# band-dsp-feather.net
KiCad netlist of a schematic drawn in EAGLE
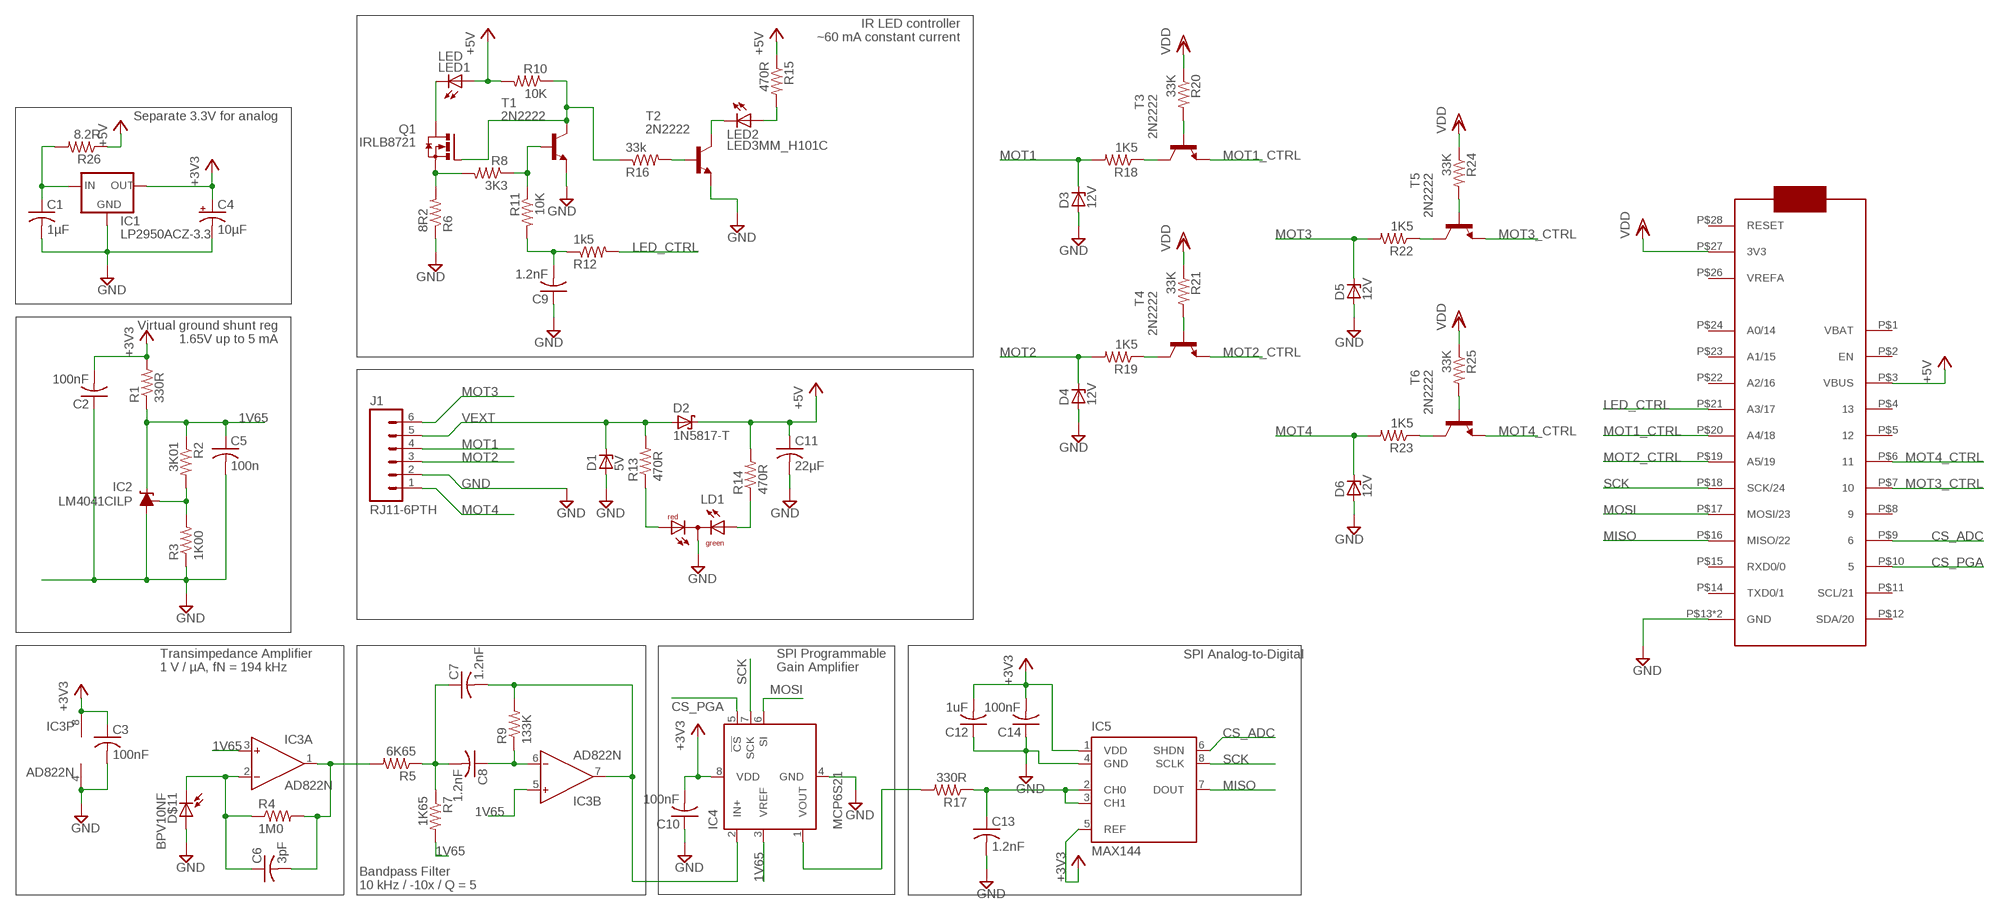
[diagram p0: schematic, sheet 1]

(export (version "E")
  (design (tool "Eeschema 10.0.6"))
  (components
    (comp (ref "C1")
      (value "1µF")
      (footprint "eagle-import:C025-030X050")
      (fields (field (name "MANF") "TDK Corporation"))
      (libsource (lib "eagle-import") (part "C-US025-030X050"))
    )
    (comp (ref "C2")
      (value "100nF")
      (footprint "eagle-import:C025-025X050")
      (fields (field (name "MANF") "Vishay BC Components"))
      (libsource (lib "eagle-import") (part "C-US025-025X050"))
    )
    (comp (ref "C3")
      (value "100nF")
      (footprint "eagle-import:C025-025X050")
      (fields (field (name "MANF") "Vishay BC Components"))
      (libsource (lib "eagle-import") (part "C-US025-025X050"))
    )
    (comp (ref "C4")
      (value "10µF")
      (footprint "eagle-import:E2,5-5")
      (fields (field (name "MANF") "AVX Corporation"))
      (libsource (lib "eagle-import") (part "CPOL-USE2.5-5"))
    )
    (comp (ref "C5")
      (value "100n")
      (footprint "eagle-import:C025-025X050")
      (fields (field (name "MANF") "Vishay BC Components"))
      (libsource (lib "eagle-import") (part "C-US025-025X050"))
    )
    (comp (ref "C6")
      (value "3pF")
      (footprint "eagle-import:C025-024X044")
      (fields (field (name "MANF") "TDK Corporation"))
      (libsource (lib "eagle-import") (part "C-US025-024X044"))
    )
    (comp (ref "C7")
      (value "1.2nF")
      (footprint "eagle-import:C025-025X050")
      (fields (field (name "MANF") "Vishay BC Components"))
      (libsource (lib "eagle-import") (part "C-US025-025X050"))
    )
    (comp (ref "C8")
      (value "1.2nF")
      (footprint "eagle-import:C025-025X050")
      (fields (field (name "MANF") "Vishay BC Components"))
      (libsource (lib "eagle-import") (part "C-US025-025X050"))
    )
    (comp (ref "C9")
      (value "1.2nF")
      (footprint "eagle-import:C025-025X050")
      (fields (field (name "MANF") "Vishay BC Components"))
      (libsource (lib "eagle-import") (part "C-US025-025X050"))
    )
    (comp (ref "C10")
      (value "100nF")
      (footprint "eagle-import:C025-025X050")
      (fields (field (name "MANF") "Vishay BC Components"))
      (libsource (lib "eagle-import") (part "C-US025-025X050"))
    )
    (comp (ref "C11")
      (value "22µF")
      (footprint "eagle-import:C050-045X075")
      (fields (field (name "MANF") "TDK Corporation"))
      (libsource (lib "eagle-import") (part "C-US050-045X075"))
    )
    (comp (ref "C12")
      (value "1uF")
      (footprint "eagle-import:C025-025X050")
      (fields (field (name "MANF") "TDK Corporation"))
      (libsource (lib "eagle-import") (part "C-US025-025X050"))
    )
    (comp (ref "C13")
      (value "1.2nF")
      (footprint "eagle-import:C025-025X050")
      (fields (field (name "MANF") "Vishay BC Components"))
      (libsource (lib "eagle-import") (part "C-US025-025X050"))
    )
    (comp (ref "C14")
      (value "100nF")
      (footprint "eagle-import:C025-025X050")
      (fields (field (name "MANF") "Vishay BC Components"))
      (libsource (lib "eagle-import") (part "C-US025-025X050"))
    )
    (comp (ref "D$11")
      (value "BPV10NF")
      (footprint "eagle-import:LED5MM")
      (fields (field (name "MANF") "Vishay Semiconductor Opto Division"))
      (libsource (lib "eagle-import") (part "BPV10NF"))
    )
    (comp (ref "D1")
      (value "5V")
      (footprint "eagle-import:F126Z10")
      (fields (field (name "MANF") "Littelfuse Inc."))
      (libsource (lib "eagle-import") (part "ZENER-DIODEF126-10"))
    )
    (comp (ref "D2")
      (value "1N5817-T")
      (footprint "eagle-import:DO41-7.6")
      (fields (field (name "MANF") "Fairchild Semiconductor"))
      (libsource (lib "eagle-import") (part "1N5817-T"))
    )
    (comp (ref "D3")
      (value "12V")
      (footprint "eagle-import:F126Z10")
      (fields (field (name "MANF") "Littelfuse Inc."))
      (libsource (lib "eagle-import") (part "ZENER-DIODEF126-10"))
    )
    (comp (ref "D4")
      (value "12V")
      (footprint "eagle-import:F126Z10")
      (fields (field (name "MANF") "Littelfuse Inc."))
      (libsource (lib "eagle-import") (part "ZENER-DIODEF126-10"))
    )
    (comp (ref "D5")
      (value "12V")
      (footprint "eagle-import:F126Z10")
      (fields (field (name "MANF") "Littelfuse Inc."))
      (libsource (lib "eagle-import") (part "ZENER-DIODEF126-10"))
    )
    (comp (ref "D6")
      (value "12V")
      (footprint "eagle-import:F126Z10")
      (fields (field (name "MANF") "Littelfuse Inc."))
      (libsource (lib "eagle-import") (part "ZENER-DIODEF126-10"))
    )
    (comp (ref "IC1")
      (value "LP2950ACZ-3.3")
      (footprint "eagle-import:TO92")
      (fields (field (name "MANF") "Texas Instruments"))
      (libsource (lib "eagle-import") (part "LP2950?ACZ-3.3"))
    )
    (comp (ref "IC2")
      (value "LM4041CILP")
      (footprint "eagle-import:LP_O-PBCY-W3")
      (fields (field (name "MANF") "Texas Instruments"))
      (libsource (lib "eagle-import") (part "LM4041ILPC"))
    )
    (comp (ref "IC3")
      (value "AD822N")
      (footprint "eagle-import:DIL08")
      (fields
        (field (name "DIGIKEY#") "AD823ANZ-ND")
        (field (name "MANF") "Analog Devices Inc.")
        (field (name "MANF#") "AD823ANZ")
      )
      (libsource (lib "eagle-import") (part "AD822N"))
    )
    (comp (ref "IC4")
      (value "MCP6S21")
      (footprint "eagle-import:DIL08")
      (fields (field (name "MANF") "Microchip Technology"))
      (libsource (lib "eagle-import") (part "MCP6S21"))
    )
    (comp (ref "IC5")
      (value "MAX144")
      (footprint "eagle-import:DIL08")
      (fields (field (name "MANF") "Maxim Integrated"))
      (libsource (lib "eagle-import") (part "MAX144"))
    )
    (comp (ref "IC6")
      (value "FEATHER_M0")
      (footprint "eagle-import:FEATHER_M0")
      (fields (field (name "MANF") "Adafruit Industries LLC"))
      (libsource (lib "eagle-import") (part "FEATHER_M0"))
    )
    (comp (ref "J1")
      (value "RJ11-6PTH")
      (footprint "eagle-import:RJ11-6")
      (fields (field (name "MANF") "Assmann WSW Components"))
      (libsource (lib "eagle-import") (part "RJ11-6PTH"))
    )
    (comp (ref "LD1")
      (value "DUOLED-RG-C")
      (footprint "eagle-import:DUOLED-C-5MM")
      (fields (field (name "MANF") "Kingbright"))
      (libsource (lib "eagle-import") (part "DUOLED-RG-C"))
    )
    (comp (ref "LED1")
      (value "LED")
      (footprint "eagle-import:1X02_3.5MM")
      (fields (field (name "MANF") "OSRAM Opto Semiconductors Inc"))
      (libsource (lib "eagle-import") (part "1X02_3.5MM_LED"))
    )
    (comp (ref "LED2")
      (value "LED3MM_H101C")
      (footprint "eagle-import:LED3MM_H101C")
      (fields (field (name "MANF") "Kingbright"))
      (libsource (lib "eagle-import") (part "LED3MM_H101C"))
    )
    (comp (ref "Q1")
      (value "IRLB8721")
      (footprint "eagle-import:TO220BV")
      (fields (field (name "MANF") "Infineon Technologies"))
      (libsource (lib "eagle-import") (part "IRLB8721"))
    )
    (comp (ref "R1")
      (value "330R")
      (footprint "eagle-import:0207_9")
      (fields (field (name "MANF") "Stackpole Electronics Inc."))
      (libsource (lib "eagle-import") (part "R-US_0207/9"))
    )
    (comp (ref "R2")
      (value "3K01")
      (footprint "eagle-import:0207_9")
      (fields (field (name "MANF") "Stackpole Electronics Inc."))
      (libsource (lib "eagle-import") (part "R-US_0207/9"))
    )
    (comp (ref "R3")
      (value "1K00")
      (footprint "eagle-import:0207_9")
      (fields (field (name "MANF") "Stackpole Electronics Inc."))
      (libsource (lib "eagle-import") (part "R-US_0207/9"))
    )
    (comp (ref "R4")
      (value "1M0")
      (footprint "eagle-import:0207_9")
      (fields (field (name "MANF") "Stackpole Electronics Inc"))
      (libsource (lib "eagle-import") (part "R-US_0207/9"))
    )
    (comp (ref "R5")
      (value "6K65")
      (footprint "eagle-import:0207_9")
      (fields (field (name "MANF") "Yageo"))
      (libsource (lib "eagle-import") (part "R-US_0207/9"))
    )
    (comp (ref "R6")
      (value "8R2")
      (footprint "eagle-import:0207_9")
      (fields (field (name "DIGIKEY#") "S8.2HCT-ND") (field (name "MANF") "Stackpole Electronics Inc."))
      (libsource (lib "eagle-import") (part "R-US_0207/9"))
    )
    (comp (ref "R7")
      (value "1K65")
      (footprint "eagle-import:0207_9")
      (fields (field (name "MANF") "Yageo"))
      (libsource (lib "eagle-import") (part "R-US_0207/9"))
    )
    (comp (ref "R8")
      (value "3K3")
      (footprint "eagle-import:0207_9")
      (fields (field (name "MANF") "Stackpole Electronics Inc"))
      (libsource (lib "eagle-import") (part "R-US_0207/9"))
    )
    (comp (ref "R9")
      (value "133K")
      (footprint "eagle-import:0207_9")
      (fields (field (name "MANF") "Yageo"))
      (libsource (lib "eagle-import") (part "R-US_0207/9"))
    )
    (comp (ref "R10")
      (value "10K")
      (footprint "eagle-import:0207_9")
      (fields (field (name "MANF") "Stackpole Electronics Inc"))
      (libsource (lib "eagle-import") (part "R-US_0207/9"))
    )
    (comp (ref "R11")
      (value "10K")
      (footprint "eagle-import:0207_9")
      (fields (field (name "MANF") "Stackpole Electronics Inc"))
      (libsource (lib "eagle-import") (part "R-US_0207/9"))
    )
    (comp (ref "R12")
      (value "1k5")
      (footprint "eagle-import:0207_9")
      (fields (field (name "MANF") "Stackpole Electronics Inc"))
      (libsource (lib "eagle-import") (part "R-US_0207/9"))
    )
    (comp (ref "R13")
      (value "470R")
      (footprint "eagle-import:0207_9")
      (fields (field (name "MANF") "Stackpole Electronics Inc."))
      (libsource (lib "eagle-import") (part "R-US_0207/9"))
    )
    (comp (ref "R14")
      (value "470R")
      (footprint "eagle-import:0207_9")
      (fields (field (name "MANF") "Stackpole Electronics Inc."))
      (libsource (lib "eagle-import") (part "R-US_0207/9"))
    )
    (comp (ref "R15")
      (value "470R")
      (footprint "eagle-import:0207_5V")
      (fields (field (name "MANF") "Stackpole Electronics Inc."))
      (libsource (lib "eagle-import") (part "R-US_0207/5V"))
    )
    (comp (ref "R16")
      (value "33k")
      (footprint "eagle-import:0207_9")
      (fields (field (name "MANF") "Stackpole Electronics Inc"))
      (libsource (lib "eagle-import") (part "R-US_0207/9"))
    )
    (comp (ref "R17")
      (value "330R")
      (footprint "eagle-import:0207_9")
      (fields (field (name "MANF") "Stackpole Electronics Inc."))
      (libsource (lib "eagle-import") (part "R-US_0207/9"))
    )
    (comp (ref "R18")
      (value "1K5")
      (footprint "eagle-import:0207_9")
      (fields (field (name "MANF") "Stackpole Electronics Inc."))
      (libsource (lib "eagle-import") (part "R-US_0207/9"))
    )
    (comp (ref "R19")
      (value "1K5")
      (footprint "eagle-import:0207_9")
      (fields (field (name "MANF") "Stackpole Electronics Inc."))
      (libsource (lib "eagle-import") (part "R-US_0207/9"))
    )
    (comp (ref "R20")
      (value "33K")
      (footprint "eagle-import:0207_9")
      (fields (field (name "MANF") "Stackpole Electronics Inc."))
      (libsource (lib "eagle-import") (part "R-US_0207/9"))
    )
    (comp (ref "R21")
      (value "33K")
      (footprint "eagle-import:0207_9")
      (fields (field (name "MANF") "Stackpole Electronics Inc."))
      (libsource (lib "eagle-import") (part "R-US_0207/9"))
    )
    (comp (ref "R22")
      (value "1K5")
      (footprint "eagle-import:0207_9")
      (fields (field (name "MANF") "Stackpole Electronics Inc."))
      (libsource (lib "eagle-import") (part "R-US_0207/9"))
    )
    (comp (ref "R23")
      (value "1K5")
      (footprint "eagle-import:0207_9")
      (fields (field (name "MANF") "Stackpole Electronics Inc."))
      (libsource (lib "eagle-import") (part "R-US_0207/9"))
    )
    (comp (ref "R24")
      (value "33K")
      (footprint "eagle-import:0207_9")
      (fields (field (name "MANF") "Stackpole Electronics Inc."))
      (libsource (lib "eagle-import") (part "R-US_0207/9"))
    )
    (comp (ref "R25")
      (value "33K")
      (footprint "eagle-import:0207_9")
      (fields (field (name "MANF") "Stackpole Electronics Inc."))
      (libsource (lib "eagle-import") (part "R-US_0207/9"))
    )
    (comp (ref "R26")
      (value "8.2R")
      (footprint "eagle-import:0207_9")
      (fields (field (name "MANF") "Stackpole Electronics Inc."))
      (libsource (lib "eagle-import") (part "R-US_0207/9"))
    )
    (comp (ref "T1")
      (value "2N2222")
      (footprint "eagle-import:TO92-EBC-OVAL")
      (fields (field (name "MANF") "Fairchild Semiconductor"))
      (libsource (lib "eagle-import") (part "2N2222"))
    )
    (comp (ref "T2")
      (value "2N2222")
      (footprint "eagle-import:TO92-EBC-OVAL")
      (fields (field (name "MANF") "Fairchild Semiconductor"))
      (libsource (lib "eagle-import") (part "2N2222"))
    )
    (comp (ref "T3")
      (value "2N2222")
      (footprint "eagle-import:TO92-EBC-OVAL")
      (fields (field (name "MANF") "Fairchild Semiconductor"))
      (libsource (lib "eagle-import") (part "2N2222"))
    )
    (comp (ref "T4")
      (value "2N2222")
      (footprint "eagle-import:TO92-EBC-OVAL")
      (fields (field (name "MANF") "Fairchild Semiconductor"))
      (libsource (lib "eagle-import") (part "2N2222"))
    )
    (comp (ref "T5")
      (value "2N2222")
      (footprint "eagle-import:TO92-EBC-OVAL")
      (fields (field (name "MANF") "Fairchild Semiconductor"))
      (libsource (lib "eagle-import") (part "2N2222"))
    )
    (comp (ref "T6")
      (value "2N2222")
      (footprint "eagle-import:TO92-EBC-OVAL")
      (fields (field (name "MANF") "Fairchild Semiconductor"))
      (libsource (lib "eagle-import") (part "2N2222"))
    )
  )
  (nets
    (net (code "1") (name "+3V3") (class "Default")
      (node (ref "C10") (pin "2") (pinfunction "2_2") (pintype "passive"))
      (node (ref "C12") (pin "2") (pinfunction "2_2") (pintype "passive"))
      (node (ref "C14") (pin "2") (pinfunction "2_2") (pintype "passive"))
      (node (ref "C2") (pin "2") (pinfunction "2_2") (pintype "passive"))
      (node (ref "C3") (pin "1") (pinfunction "1_1") (pintype "passive"))
      (node (ref "C4") (pin "+") (pinfunction "+_+") (pintype "passive"))
      (node (ref "IC1") (pin "1") (pinfunction "OUT_1") (pintype "passive"))
      (node (ref "IC3") (pin "8") (pinfunction "V+_8") (pintype "power_in"))
      (node (ref "IC4") (pin "8") (pinfunction "VDD_8") (pintype "power_in"))
      (node (ref "IC5") (pin "1") (pinfunction "VDD_1") (pintype "power_in"))
      (node (ref "IC5") (pin "5") (pinfunction "REF_5") (pintype "input"))
      (node (ref "R1") (pin "2") (pinfunction "2_2") (pintype "passive"))
    )
    (net (code "2") (name "+5V") (class "Default")
      (node (ref "C11") (pin "1") (pinfunction "1_1") (pintype "passive"))
      (node (ref "D2") (pin "C") (pinfunction "C_C") (pintype "passive"))
      (node (ref "IC6") (pin "P$3") (pinfunction "VBUS_P$3") (pintype "bidirectional"))
      (node (ref "LED1") (pin "1A") (pinfunction "A_1A") (pintype "passive"))
      (node (ref "R10") (pin "2") (pinfunction "2_2") (pintype "passive"))
      (node (ref "R14") (pin "2") (pinfunction "2_2") (pintype "passive"))
      (node (ref "R15") (pin "1") (pinfunction "1_1") (pintype "passive"))
      (node (ref "R26") (pin "1") (pinfunction "1_1") (pintype "passive"))
    )
    (net (code "3") (name "/1V65") (class "Default")
      (node (ref "C5") (pin "1") (pinfunction "1_1") (pintype "passive"))
      (node (ref "IC2") (pin "2") (pinfunction "C_2") (pintype "passive"))
      (node (ref "IC3") (pin "3") (pinfunction "IN+_3") (pintype "input"))
      (node (ref "IC3") (pin "5") (pinfunction "IN+_5") (pintype "input"))
      (node (ref "IC4") (pin "3") (pinfunction "VREF_3") (pintype "input"))
      (node (ref "R1") (pin "1") (pinfunction "1_1") (pintype "passive"))
      (node (ref "R2") (pin "1") (pinfunction "1_1") (pintype "passive"))
      (node (ref "R7") (pin "2") (pinfunction "2_2") (pintype "passive"))
    )
    (net (code "4") (name "/CS_ADC") (class "Default")
      (node (ref "IC5") (pin "6") (pinfunction "SHDN_6") (pintype "input"))
      (node (ref "IC6") (pin "P$9") (pinfunction "6_P$9") (pintype "bidirectional"))
    )
    (net (code "5") (name "/CS_PGA") (class "Default")
      (node (ref "IC4") (pin "5") (pinfunction "~{CS}_5") (pintype "input"))
      (node (ref "IC6") (pin "P$10") (pinfunction "5_P$10") (pintype "bidirectional"))
    )
    (net (code "6") (name "/LED_CTRL") (class "Default")
      (node (ref "IC6") (pin "P$21") (pinfunction "A3/17_P$21") (pintype "bidirectional"))
      (node (ref "R12") (pin "2") (pinfunction "2_2") (pintype "passive"))
    )
    (net (code "7") (name "/MISO") (class "Default")
      (node (ref "IC5") (pin "7") (pinfunction "DOUT_7") (pintype "input"))
      (node (ref "IC6") (pin "P$16") (pinfunction "MISO/22_P$16") (pintype "bidirectional"))
    )
    (net (code "8") (name "/MOSI") (class "Default")
      (node (ref "IC4") (pin "6") (pinfunction "SI_6") (pintype "input"))
      (node (ref "IC6") (pin "P$17") (pinfunction "MOSI/23_P$17") (pintype "bidirectional"))
    )
    (net (code "9") (name "/MOT1") (class "Default")
      (node (ref "D3") (pin "C") (pinfunction "C_C") (pintype "passive"))
      (node (ref "J1") (pin "4") (pinfunction "4_4") (pintype "passive"))
      (node (ref "R18") (pin "2") (pinfunction "2_2") (pintype "passive"))
    )
    (net (code "10") (name "/MOT1_CTRL") (class "Default")
      (node (ref "IC6") (pin "P$20") (pinfunction "A4/18_P$20") (pintype "bidirectional"))
      (node (ref "T3") (pin "E") (pinfunction "E_E") (pintype "passive"))
    )
    (net (code "11") (name "/MOT2") (class "Default")
      (node (ref "D4") (pin "C") (pinfunction "C_C") (pintype "passive"))
      (node (ref "J1") (pin "3") (pinfunction "3_3") (pintype "passive"))
      (node (ref "R19") (pin "2") (pinfunction "2_2") (pintype "passive"))
    )
    (net (code "12") (name "/MOT2_CTRL") (class "Default")
      (node (ref "IC6") (pin "P$19") (pinfunction "A5/19_P$19") (pintype "bidirectional"))
      (node (ref "T4") (pin "E") (pinfunction "E_E") (pintype "passive"))
    )
    (net (code "13") (name "/MOT3") (class "Default")
      (node (ref "D5") (pin "C") (pinfunction "C_C") (pintype "passive"))
      (node (ref "J1") (pin "6") (pinfunction "6_6") (pintype "passive"))
      (node (ref "R22") (pin "2") (pinfunction "2_2") (pintype "passive"))
    )
    (net (code "14") (name "/MOT3_CTRL") (class "Default")
      (node (ref "IC6") (pin "P$7") (pinfunction "10_P$7") (pintype "bidirectional"))
      (node (ref "T5") (pin "E") (pinfunction "E_E") (pintype "passive"))
    )
    (net (code "15") (name "/MOT4") (class "Default")
      (node (ref "D6") (pin "C") (pinfunction "C_C") (pintype "passive"))
      (node (ref "J1") (pin "1") (pinfunction "1_1") (pintype "passive"))
      (node (ref "R23") (pin "2") (pinfunction "2_2") (pintype "passive"))
    )
    (net (code "16") (name "/MOT4_CTRL") (class "Default")
      (node (ref "IC6") (pin "P$6") (pinfunction "11_P$6") (pintype "bidirectional"))
      (node (ref "T6") (pin "E") (pinfunction "E_E") (pintype "passive"))
    )
    (net (code "17") (name "/SCK") (class "Default")
      (node (ref "IC4") (pin "7") (pinfunction "SCK_7") (pintype "input"))
      (node (ref "IC5") (pin "8") (pinfunction "SCLK_8") (pintype "input"))
      (node (ref "IC6") (pin "P$18") (pinfunction "SCK/24_P$18") (pintype "bidirectional"))
    )
    (net (code "18") (name "/VEXT") (class "Default")
      (node (ref "D1") (pin "C") (pinfunction "C_C") (pintype "passive"))
      (node (ref "D2") (pin "A") (pinfunction "A_A") (pintype "passive"))
      (node (ref "J1") (pin "5") (pinfunction "5_5") (pintype "passive"))
      (node (ref "R13") (pin "2") (pinfunction "2_2") (pintype "passive"))
    )
    (net (code "19") (name "GND") (class "Default")
      (node (ref "C1") (pin "2") (pinfunction "2_2") (pintype "passive"))
      (node (ref "C10") (pin "1") (pinfunction "1_1") (pintype "passive"))
      (node (ref "C11") (pin "2") (pinfunction "2_2") (pintype "passive"))
      (node (ref "C12") (pin "1") (pinfunction "1_1") (pintype "passive"))
      (node (ref "C13") (pin "2") (pinfunction "2_2") (pintype "passive"))
      (node (ref "C14") (pin "1") (pinfunction "1_1") (pintype "passive"))
      (node (ref "C2") (pin "1") (pinfunction "1_1") (pintype "passive"))
      (node (ref "C3") (pin "2") (pinfunction "2_2") (pintype "passive"))
      (node (ref "C4") (pin "-") (pinfunction "-_-") (pintype "passive"))
      (node (ref "C5") (pin "2") (pinfunction "2_2") (pintype "passive"))
      (node (ref "C9") (pin "1") (pinfunction "1_1") (pintype "passive"))
      (node (ref "D$11") (pin "A") (pinfunction "A_A") (pintype "passive"))
      (node (ref "D1") (pin "A") (pinfunction "A_A") (pintype "passive"))
      (node (ref "D3") (pin "A") (pinfunction "A_A") (pintype "passive"))
      (node (ref "D4") (pin "A") (pinfunction "A_A") (pintype "passive"))
      (node (ref "D5") (pin "A") (pinfunction "A_A") (pintype "passive"))
      (node (ref "D6") (pin "A") (pinfunction "A_A") (pintype "passive"))
      (node (ref "IC1") (pin "2") (pinfunction "GND_2") (pintype "input"))
      (node (ref "IC2") (pin "3") (pinfunction "A_3") (pintype "passive"))
      (node (ref "IC3") (pin "4") (pinfunction "V-_4") (pintype "power_in"))
      (node (ref "IC4") (pin "4") (pinfunction "GND_4") (pintype "power_in"))
      (node (ref "IC5") (pin "4") (pinfunction "GND_4") (pintype "power_in"))
      (node (ref "IC6") (pin "P$13") (pinfunction "GND_P$13") (pintype "bidirectional"))
      (node (ref "IC6") (pin "P$25") (pinfunction "GND_P$25") (pintype "bidirectional"))
      (node (ref "J1") (pin "2") (pinfunction "2_2") (pintype "passive"))
      (node (ref "LD1") (pin "C") (pinfunction "C_C") (pintype "passive"))
      (node (ref "R3") (pin "1") (pinfunction "1_1") (pintype "passive"))
      (node (ref "R6") (pin "1") (pinfunction "1_1") (pintype "passive"))
      (node (ref "T1") (pin "E") (pinfunction "E_E") (pintype "passive"))
      (node (ref "T2") (pin "E") (pinfunction "E_E") (pintype "passive"))
    )
    (net (code "20") (name "Net-(C7-Pad1)") (class "Default")
      (node (ref "C7") (pin "1") (pinfunction "1_1") (pintype "passive"))
      (node (ref "C8") (pin "2") (pinfunction "2_2") (pintype "passive"))
      (node (ref "R5") (pin "1") (pinfunction "1_1") (pintype "passive"))
      (node (ref "R7") (pin "1") (pinfunction "1_1") (pintype "passive"))
    )
    (net (code "21") (name "Net-(C9-Pad2)") (class "Default")
      (node (ref "C9") (pin "2") (pinfunction "2_2") (pintype "passive"))
      (node (ref "R11") (pin "2") (pinfunction "2_2") (pintype "passive"))
      (node (ref "R12") (pin "1") (pinfunction "1_1") (pintype "passive"))
    )
    (net (code "22") (name "Net-(IC1-IN)") (class "Default")
      (node (ref "C1") (pin "1") (pinfunction "1_1") (pintype "passive"))
      (node (ref "IC1") (pin "3") (pinfunction "IN_3") (pintype "input"))
      (node (ref "R26") (pin "2") (pinfunction "2_2") (pintype "passive"))
    )
    (net (code "23") (name "Net-(IC2-FB)") (class "Default")
      (node (ref "IC2") (pin "1") (pinfunction "FB_1") (pintype "passive"))
      (node (ref "R2") (pin "2") (pinfunction "2_2") (pintype "passive"))
      (node (ref "R3") (pin "2") (pinfunction "2_2") (pintype "passive"))
    )
    (net (code "24") (name "Net-(IC3A-IN-)") (class "Default")
      (node (ref "C6") (pin "1") (pinfunction "1_1") (pintype "passive"))
      (node (ref "D$11") (pin "K") (pinfunction "K_K") (pintype "passive"))
      (node (ref "IC3") (pin "2") (pinfunction "IN-_2") (pintype "input"))
      (node (ref "R4") (pin "1") (pinfunction "1_1") (pintype "passive"))
    )
    (net (code "25") (name "Net-(IC3A-OUT)") (class "Default")
      (node (ref "C6") (pin "2") (pinfunction "2_2") (pintype "passive"))
      (node (ref "IC3") (pin "1") (pinfunction "OUT_1") (pintype "output"))
      (node (ref "R4") (pin "2") (pinfunction "2_2") (pintype "passive"))
      (node (ref "R5") (pin "2") (pinfunction "2_2") (pintype "passive"))
    )
    (net (code "26") (name "Net-(IC3B-IN-)") (class "Default")
      (node (ref "C8") (pin "1") (pinfunction "1_1") (pintype "passive"))
      (node (ref "IC3") (pin "6") (pinfunction "IN-_6") (pintype "input"))
      (node (ref "R9") (pin "1") (pinfunction "1_1") (pintype "passive"))
    )
    (net (code "27") (name "Net-(IC3B-OUT)") (class "Default")
      (node (ref "C7") (pin "2") (pinfunction "2_2") (pintype "passive"))
      (node (ref "IC3") (pin "7") (pinfunction "OUT_7") (pintype "output"))
      (node (ref "IC4") (pin "2") (pinfunction "IN+_2") (pintype "input"))
      (node (ref "R9") (pin "2") (pinfunction "2_2") (pintype "passive"))
    )
    (net (code "28") (name "Net-(IC4-VOUT)") (class "Default")
      (node (ref "IC4") (pin "1") (pinfunction "VOUT_1") (pintype "output"))
      (node (ref "R17") (pin "2") (pinfunction "2_2") (pintype "passive"))
    )
    (net (code "29") (name "Net-(IC5-CH0)") (class "Default")
      (node (ref "C13") (pin "1") (pinfunction "1_1") (pintype "passive"))
      (node (ref "IC5") (pin "2") (pinfunction "CH0_2") (pintype "input"))
      (node (ref "IC5") (pin "3") (pinfunction "CH1_3") (pintype "input"))
      (node (ref "R17") (pin "1") (pinfunction "1_1") (pintype "passive"))
    )
    (net (code "30") (name "Net-(LD1-AG)") (class "Default")
      (node (ref "LD1") (pin "AX") (pinfunction "AG_AX") (pintype "passive"))
      (node (ref "R14") (pin "1") (pinfunction "1_1") (pintype "passive"))
    )
    (net (code "31") (name "Net-(LD1-PadAR)") (class "Default")
      (node (ref "LD1") (pin "AR") (pinfunction "AR_AR") (pintype "passive"))
      (node (ref "R13") (pin "1") (pinfunction "1_1") (pintype "passive"))
    )
    (net (code "32") (name "Net-(LED1-K)") (class "Default")
      (node (ref "LED1") (pin "2K") (pinfunction "K_2K") (pintype "passive"))
      (node (ref "Q1") (pin "D") (pinfunction "D_D") (pintype "passive"))
    )
    (net (code "33") (name "Net-(LED2-PadA)") (class "Default")
      (node (ref "LED2") (pin "A") (pinfunction "A_A") (pintype "passive"))
      (node (ref "R15") (pin "2") (pinfunction "2_2") (pintype "passive"))
    )
    (net (code "34") (name "Net-(LED2-PadK)") (class "Default")
      (node (ref "LED2") (pin "K") (pinfunction "K_K") (pintype "passive"))
      (node (ref "T2") (pin "C") (pinfunction "C_C") (pintype "passive"))
    )
    (net (code "35") (name "Net-(Q1-PadG)") (class "Default")
      (node (ref "Q1") (pin "G") (pinfunction "G_G") (pintype "passive"))
      (node (ref "R10") (pin "1") (pinfunction "1_1") (pintype "passive"))
      (node (ref "R16") (pin "1") (pinfunction "1_1") (pintype "passive"))
      (node (ref "T1") (pin "C") (pinfunction "C_C") (pintype "passive"))
    )
    (net (code "36") (name "Net-(Q1-PadS)") (class "Default")
      (node (ref "Q1") (pin "S") (pinfunction "S_S") (pintype "passive"))
      (node (ref "R6") (pin "2") (pinfunction "2_2") (pintype "passive"))
      (node (ref "R8") (pin "2") (pinfunction "2_2") (pintype "passive"))
    )
    (net (code "37") (name "Net-(R11-Pad1)") (class "Default")
      (node (ref "R11") (pin "1") (pinfunction "1_1") (pintype "passive"))
      (node (ref "R8") (pin "1") (pinfunction "1_1") (pintype "passive"))
      (node (ref "T1") (pin "B") (pinfunction "B_B") (pintype "passive"))
    )
    (net (code "38") (name "Net-(R16-Pad2)") (class "Default")
      (node (ref "R16") (pin "2") (pinfunction "2_2") (pintype "passive"))
      (node (ref "T2") (pin "B") (pinfunction "B_B") (pintype "passive"))
    )
    (net (code "39") (name "Net-(R18-Pad1)") (class "Default")
      (node (ref "R18") (pin "1") (pinfunction "1_1") (pintype "passive"))
      (node (ref "T3") (pin "C") (pinfunction "C_C") (pintype "passive"))
    )
    (net (code "40") (name "Net-(R19-Pad1)") (class "Default")
      (node (ref "R19") (pin "1") (pinfunction "1_1") (pintype "passive"))
      (node (ref "T4") (pin "C") (pinfunction "C_C") (pintype "passive"))
    )
    (net (code "41") (name "Net-(R20-Pad2)") (class "Default")
      (node (ref "R20") (pin "2") (pinfunction "2_2") (pintype "passive"))
      (node (ref "T3") (pin "B") (pinfunction "B_B") (pintype "passive"))
    )
    (net (code "42") (name "Net-(R21-Pad2)") (class "Default")
      (node (ref "R21") (pin "2") (pinfunction "2_2") (pintype "passive"))
      (node (ref "T4") (pin "B") (pinfunction "B_B") (pintype "passive"))
    )
    (net (code "43") (name "Net-(R22-Pad1)") (class "Default")
      (node (ref "R22") (pin "1") (pinfunction "1_1") (pintype "passive"))
      (node (ref "T5") (pin "C") (pinfunction "C_C") (pintype "passive"))
    )
    (net (code "44") (name "Net-(R23-Pad1)") (class "Default")
      (node (ref "R23") (pin "1") (pinfunction "1_1") (pintype "passive"))
      (node (ref "T6") (pin "C") (pinfunction "C_C") (pintype "passive"))
    )
    (net (code "45") (name "Net-(R24-Pad2)") (class "Default")
      (node (ref "R24") (pin "2") (pinfunction "2_2") (pintype "passive"))
      (node (ref "T5") (pin "B") (pinfunction "B_B") (pintype "passive"))
    )
    (net (code "46") (name "Net-(R25-Pad2)") (class "Default")
      (node (ref "R25") (pin "2") (pinfunction "2_2") (pintype "passive"))
      (node (ref "T6") (pin "B") (pinfunction "B_B") (pintype "passive"))
    )
    (net (code "47") (name "VDD") (class "Default")
      (node (ref "IC6") (pin "P$27") (pinfunction "3V3_P$27") (pintype "bidirectional"))
      (node (ref "R20") (pin "1") (pinfunction "1_1") (pintype "passive"))
      (node (ref "R21") (pin "1") (pinfunction "1_1") (pintype "passive"))
      (node (ref "R24") (pin "1") (pinfunction "1_1") (pintype "passive"))
      (node (ref "R25") (pin "1") (pinfunction "1_1") (pintype "passive"))
    )
    (net (code "48") (name "unconnected-(IC6-9-PadP$8)") (class "Default")
      (node (ref "IC6") (pin "P$8") (pinfunction "9_P$8") (pintype "bidirectional"))
    )
    (net (code "49") (name "unconnected-(IC6-12-PadP$5)") (class "Default")
      (node (ref "IC6") (pin "P$5") (pinfunction "12_P$5") (pintype "bidirectional"))
    )
    (net (code "50") (name "unconnected-(IC6-13-PadP$4)") (class "Default")
      (node (ref "IC6") (pin "P$4") (pinfunction "13_P$4") (pintype "bidirectional"))
    )
    (net (code "51") (name "unconnected-(IC6-A0{slash}14-PadP$24)") (class "Default")
      (node (ref "IC6") (pin "P$24") (pinfunction "A0/14_P$24") (pintype "bidirectional"))
    )
    (net (code "52") (name "unconnected-(IC6-A1{slash}15-PadP$23)") (class "Default")
      (node (ref "IC6") (pin "P$23") (pinfunction "A1/15_P$23") (pintype "bidirectional"))
    )
    (net (code "53") (name "unconnected-(IC6-A2{slash}16-PadP$22)") (class "Default")
      (node (ref "IC6") (pin "P$22") (pinfunction "A2/16_P$22") (pintype "bidirectional"))
    )
    (net (code "54") (name "unconnected-(IC6-EN-PadP$2)") (class "Default")
      (node (ref "IC6") (pin "P$2") (pinfunction "EN_P$2") (pintype "bidirectional"))
    )
    (net (code "55") (name "unconnected-(IC6-RESET-PadP$28)") (class "Default")
      (node (ref "IC6") (pin "P$28") (pinfunction "RESET_P$28") (pintype "bidirectional"))
    )
    (net (code "56") (name "unconnected-(IC6-RXD0{slash}0-PadP$15)") (class "Default")
      (node (ref "IC6") (pin "P$15") (pinfunction "RXD0/0_P$15") (pintype "bidirectional"))
    )
    (net (code "57") (name "unconnected-(IC6-SCL{slash}21-PadP$11)") (class "Default")
      (node (ref "IC6") (pin "P$11") (pinfunction "SCL/21_P$11") (pintype "bidirectional"))
    )
    (net (code "58") (name "unconnected-(IC6-SDA{slash}20-PadP$12)") (class "Default")
      (node (ref "IC6") (pin "P$12") (pinfunction "SDA/20_P$12") (pintype "bidirectional"))
    )
    (net (code "59") (name "unconnected-(IC6-TXD0{slash}1-PadP$14)") (class "Default")
      (node (ref "IC6") (pin "P$14") (pinfunction "TXD0/1_P$14") (pintype "bidirectional"))
    )
    (net (code "60") (name "unconnected-(IC6-VBAT-PadP$1)") (class "Default")
      (node (ref "IC6") (pin "P$1") (pinfunction "VBAT_P$1") (pintype "bidirectional"))
    )
    (net (code "61") (name "unconnected-(IC6-VREFA-PadP$26)") (class "Default")
      (node (ref "IC6") (pin "P$26") (pinfunction "VREFA_P$26") (pintype "bidirectional"))
    )
  )
)
